# mixer_lfo_pots.net
KiCad netlist of a schematic drawn in EAGLE
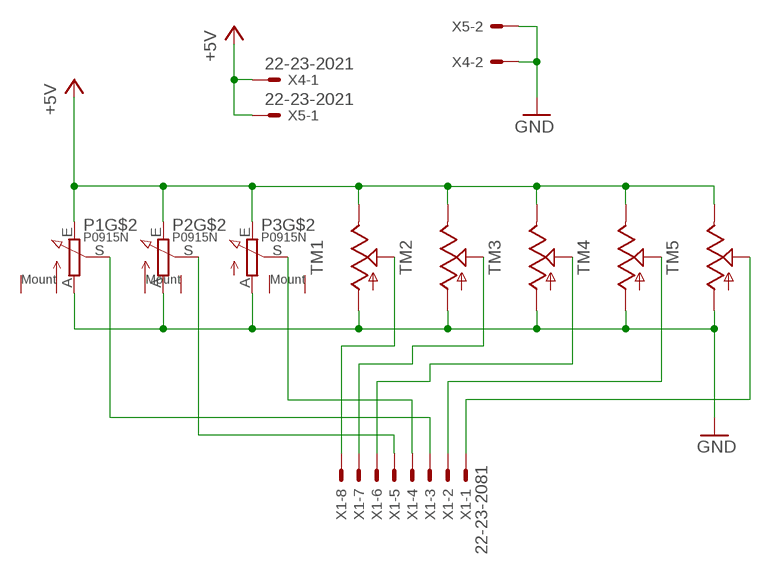
[diagram p0: schematic, sheet 1]

(export (version "E")
  (design (tool "Eeschema 10.0.6"))
  (components
    (comp (ref "P1")
      (value "P0915N")
      (footprint "eagle-import:P0915N")
      (libsource (lib "eagle-import") (part "P0915N"))
    )
    (comp (ref "P2")
      (value "P0915N")
      (footprint "eagle-import:P0915N")
      (libsource (lib "eagle-import") (part "P0915N"))
    )
    (comp (ref "P3")
      (value "P0915N")
      (footprint "eagle-import:P0915N")
      (libsource (lib "eagle-import") (part "P0915N"))
    )
    (comp (ref "TM1")
      (value "TRIMSLIDE60")
      (footprint "eagle-import:SLIDEPOT-60")
      (libsource (lib "eagle-import") (part "TRIMSLIDE60"))
    )
    (comp (ref "TM2")
      (value "TRIMSLIDE60")
      (footprint "eagle-import:SLIDEPOT-60")
      (libsource (lib "eagle-import") (part "TRIMSLIDE60"))
    )
    (comp (ref "TM3")
      (value "TRIMSLIDE60")
      (footprint "eagle-import:SLIDEPOT-60")
      (libsource (lib "eagle-import") (part "TRIMSLIDE60"))
    )
    (comp (ref "TM4")
      (value "TRIMSLIDE60")
      (footprint "eagle-import:SLIDEPOT-60")
      (libsource (lib "eagle-import") (part "TRIMSLIDE60"))
    )
    (comp (ref "TM5")
      (value "TRIMSLIDE60")
      (footprint "eagle-import:SLIDEPOT-60")
      (libsource (lib "eagle-import") (part "TRIMSLIDE60"))
    )
    (comp (ref "X1")
      (value "22-23-2081")
      (footprint "eagle-import:22-23-2081")
      (fields (field (name "MF") "MOLEX"))
      (libsource (lib "eagle-import") (part "22-23-2081"))
    )
    (comp (ref "X4")
      (value "22-23-2021")
      (footprint "eagle-import:22-23-2021")
      (fields (field (name "MF") "MOLEX"))
      (libsource (lib "eagle-import") (part "22-23-2021"))
    )
    (comp (ref "X5")
      (value "22-23-2021")
      (footprint "eagle-import:22-23-2021")
      (fields (field (name "MF") "MOLEX"))
      (libsource (lib "eagle-import") (part "22-23-2021"))
    )
  )
  (nets
    (net (code "1") (name "+5V") (class "Default")
      (node (ref "P1") (pin "E") (pinfunction "E_E") (pintype "passive"))
      (node (ref "P2") (pin "E") (pinfunction "E_E") (pintype "passive"))
      (node (ref "P3") (pin "E") (pinfunction "E_E") (pintype "passive"))
      (node (ref "TM1") (pin "B") (pinfunction "B_B") (pintype "passive"))
      (node (ref "TM2") (pin "B") (pinfunction "B_B") (pintype "passive"))
      (node (ref "TM3") (pin "B") (pinfunction "B_B") (pintype "passive"))
      (node (ref "TM4") (pin "B") (pinfunction "B_B") (pintype "passive"))
      (node (ref "TM5") (pin "B") (pinfunction "B_B") (pintype "passive"))
      (node (ref "X4") (pin "1") (pinfunction "S_1") (pintype "passive"))
      (node (ref "X5") (pin "1") (pinfunction "S_1") (pintype "passive"))
    )
    (net (code "2") (name "GND") (class "Default")
      (node (ref "P1") (pin "A") (pinfunction "A_A") (pintype "passive"))
      (node (ref "P2") (pin "A") (pinfunction "A_A") (pintype "passive"))
      (node (ref "P3") (pin "A") (pinfunction "A_A") (pintype "passive"))
      (node (ref "TM1") (pin "A") (pinfunction "A_A") (pintype "passive"))
      (node (ref "TM2") (pin "A") (pinfunction "A_A") (pintype "passive"))
      (node (ref "TM3") (pin "A") (pinfunction "A_A") (pintype "passive"))
      (node (ref "TM4") (pin "A") (pinfunction "A_A") (pintype "passive"))
      (node (ref "TM5") (pin "A") (pinfunction "A_A") (pintype "passive"))
      (node (ref "X4") (pin "2") (pinfunction "S_2") (pintype "passive"))
      (node (ref "X5") (pin "2") (pinfunction "S_2") (pintype "passive"))
    )
    (net (code "3") (name "Net-(X1A-S)") (class "Default")
      (node (ref "TM5") (pin "WIPER") (pinfunction "WIPER_WIPER") (pintype "passive"))
      (node (ref "X1") (pin "1") (pinfunction "S_1") (pintype "passive"))
    )
    (net (code "4") (name "Net-(X1B-S)") (class "Default")
      (node (ref "TM4") (pin "WIPER") (pinfunction "WIPER_WIPER") (pintype "passive"))
      (node (ref "X1") (pin "2") (pinfunction "S_2") (pintype "passive"))
    )
    (net (code "5") (name "Net-(X1C-S)") (class "Default")
      (node (ref "P1") (pin "S") (pinfunction "S_S") (pintype "passive"))
      (node (ref "X1") (pin "3") (pinfunction "S_3") (pintype "passive"))
    )
    (net (code "6") (name "Net-(X1D-S)") (class "Default")
      (node (ref "P3") (pin "S") (pinfunction "S_S") (pintype "passive"))
      (node (ref "X1") (pin "4") (pinfunction "S_4") (pintype "passive"))
    )
    (net (code "7") (name "Net-(X1E-S)") (class "Default")
      (node (ref "P2") (pin "S") (pinfunction "S_S") (pintype "passive"))
      (node (ref "X1") (pin "5") (pinfunction "S_5") (pintype "passive"))
    )
    (net (code "8") (name "Net-(X1F-S)") (class "Default")
      (node (ref "TM3") (pin "WIPER") (pinfunction "WIPER_WIPER") (pintype "passive"))
      (node (ref "X1") (pin "6") (pinfunction "S_6") (pintype "passive"))
    )
    (net (code "9") (name "Net-(X1G-S)") (class "Default")
      (node (ref "TM2") (pin "WIPER") (pinfunction "WIPER_WIPER") (pintype "passive"))
      (node (ref "X1") (pin "7") (pinfunction "S_7") (pintype "passive"))
    )
    (net (code "10") (name "Net-(X1H-S)") (class "Default")
      (node (ref "TM1") (pin "WIPER") (pinfunction "WIPER_WIPER") (pintype "passive"))
      (node (ref "X1") (pin "8") (pinfunction "S_8") (pintype "passive"))
    )
    (net (code "11") (name "unconnected-(P1A-GND-PadGND@1)") (class "Default")
      (node (ref "P1") (pin "GND@1") (pinfunction "GND_GND@1") (pintype "passive"))
    )
    (net (code "12") (name "unconnected-(P1A-GND-PadGND@2)") (class "Default")
      (node (ref "P1") (pin "GND@2") (pinfunction "GND_GND@2") (pintype "passive"))
    )
    (net (code "13") (name "unconnected-(P2A-GND-PadGND@1)") (class "Default")
      (node (ref "P2") (pin "GND@1") (pinfunction "GND_GND@1") (pintype "passive"))
    )
    (net (code "14") (name "unconnected-(P2A-GND-PadGND@2)") (class "Default")
      (node (ref "P2") (pin "GND@2") (pinfunction "GND_GND@2") (pintype "passive"))
    )
    (net (code "15") (name "unconnected-(P3A-GND-PadGND@1)") (class "Default")
      (node (ref "P3") (pin "GND@1") (pinfunction "GND_GND@1") (pintype "passive"))
    )
    (net (code "16") (name "unconnected-(P3A-GND-PadGND@2)") (class "Default")
      (node (ref "P3") (pin "GND@2") (pinfunction "GND_GND@2") (pintype "passive"))
    )
  )
)
